# i2c-7segled-SOIC.net
KiCad netlist of a schematic drawn in EAGLE
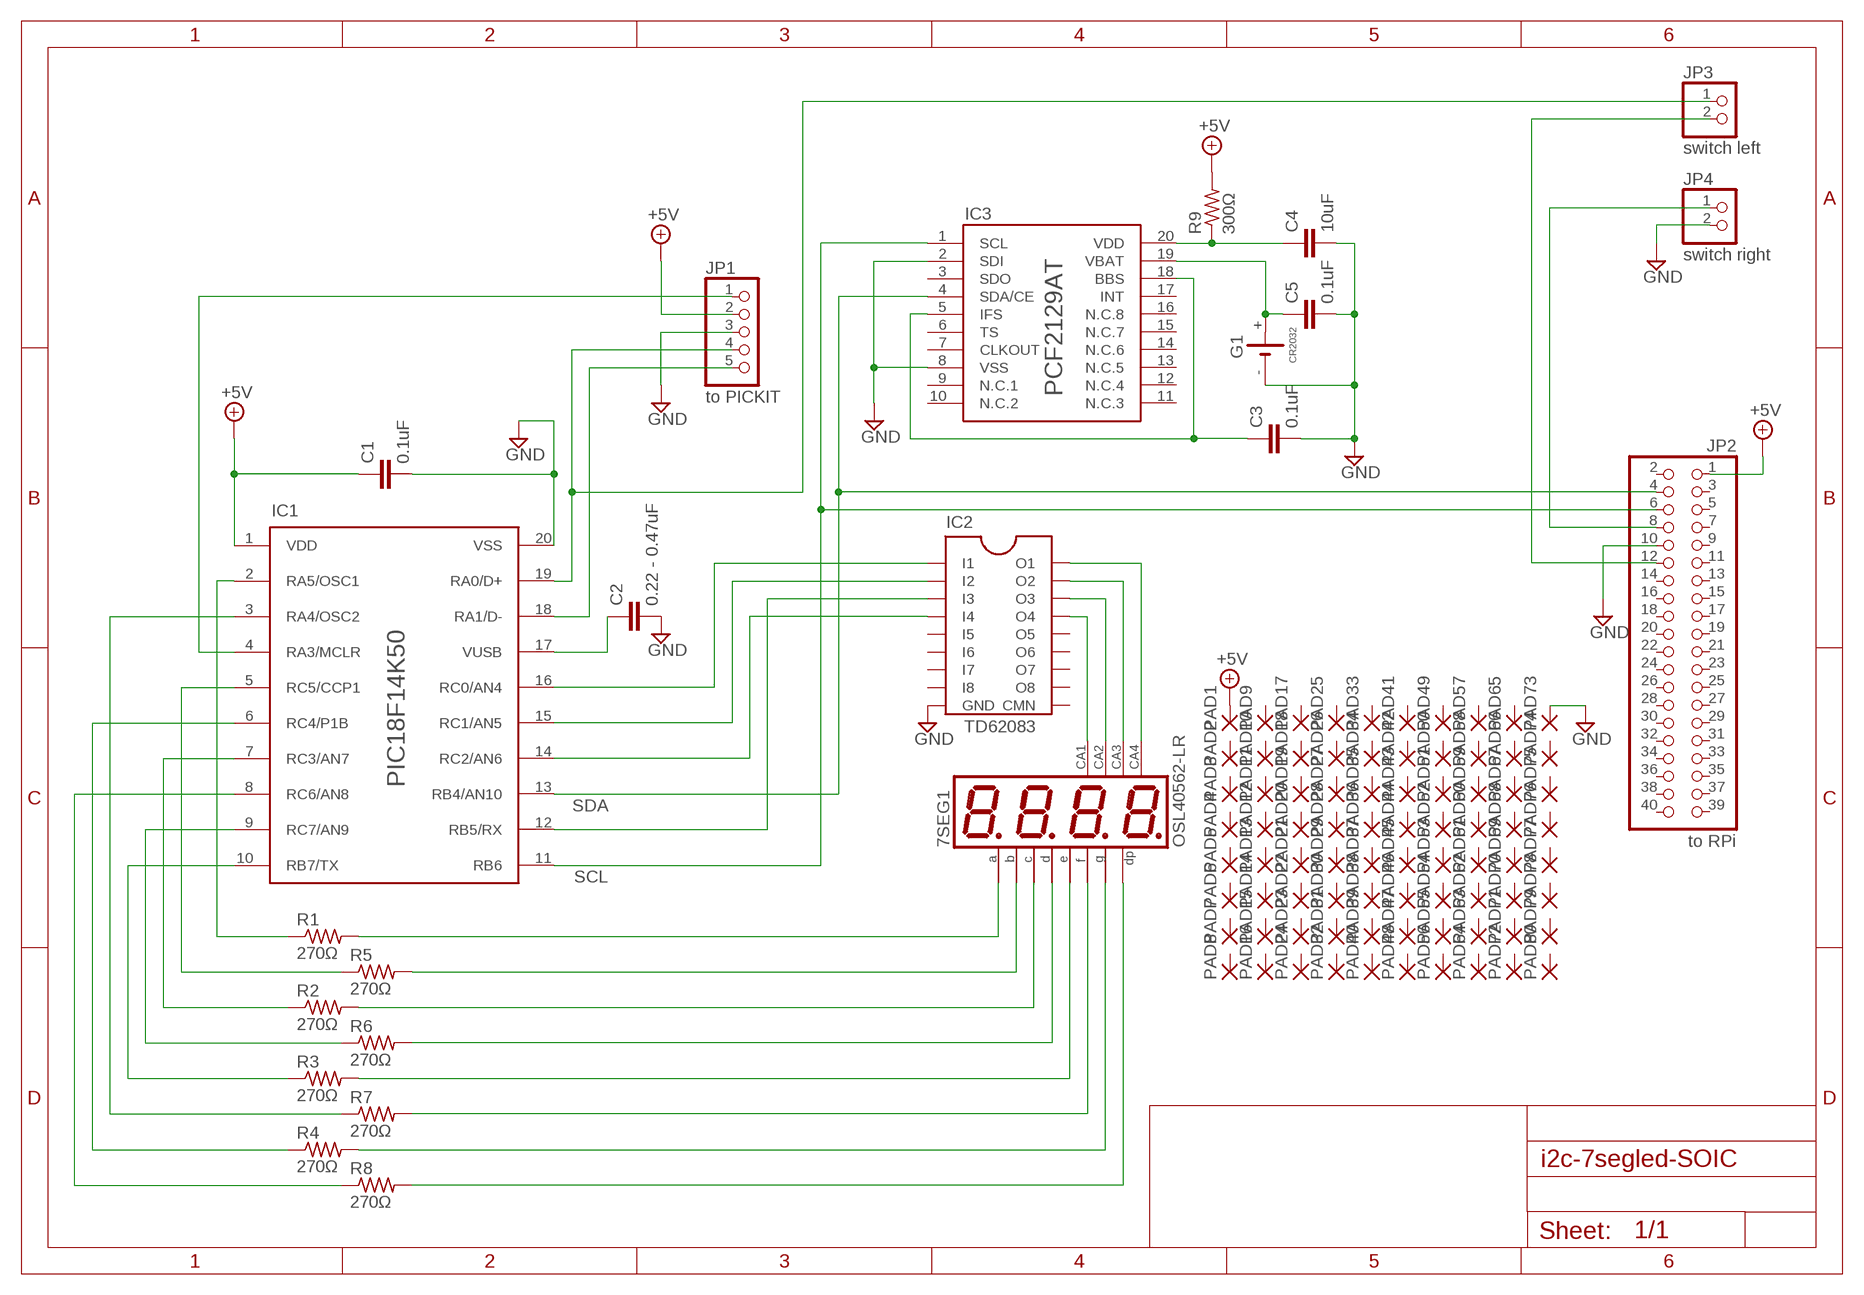
[diagram p0: schematic, sheet 1]

(export (version "E")
  (design (tool "Eeschema 10.0.6"))
  (components
    (comp (ref "7SEG1")
      (value "OSL40562-LR")
      (footprint "eagle-import:OSL40562")
      (libsource (lib "eagle-import") (part "OSL40562-?IR"))
    )
    (comp (ref "C1")
      (value "0.1uF")
      (footprint "eagle-import:C0504")
      (libsource (lib "eagle-import") (part "C-EUC0504"))
    )
    (comp (ref "C2")
      (value "0.22 - 0.47uF")
      (footprint "eagle-import:C0504")
      (libsource (lib "eagle-import") (part "C-EUC0504"))
    )
    (comp (ref "C3")
      (value "0.1uF")
      (footprint "eagle-import:C0504")
      (libsource (lib "eagle-import") (part "C-EUC0504"))
    )
    (comp (ref "C4")
      (value "10uF")
      (footprint "eagle-import:C0504")
      (libsource (lib "eagle-import") (part "C-EUC0504"))
    )
    (comp (ref "C5")
      (value "0.1uF")
      (footprint "eagle-import:C0504")
      (libsource (lib "eagle-import") (part "C-EUC0504"))
    )
    (comp (ref "G1")
      (value "CR2032")
      (footprint "eagle-import:HU2032")
      (libsource (lib "eagle-import") (part "HU2032"))
    )
    (comp (ref "IC1")
      (value "PIC18F14K50")
      (footprint "eagle-import:SO20")
      (libsource (lib "eagle-import") (part "PIC18F14K50-SO"))
    )
    (comp (ref "IC2")
      (value "TD62083")
      (footprint "eagle-import:SO18")
      (libsource (lib "eagle-import") (part "TD62083"))
    )
    (comp (ref "IC3")
      (value "PCF2129AT")
      (footprint "eagle-import:SO20")
      (libsource (lib "eagle-import") (part "PCF2129AT"))
    )
    (comp (ref "JP1")
      (value "to PICKIT")
      (footprint "eagle-import:1X05")
      (libsource (lib "eagle-import") (part "PINHD-1X5"))
    )
    (comp (ref "JP2")
      (value "to RPi")
      (footprint "eagle-import:2X20")
      (libsource (lib "eagle-import") (part "PINHD-2X20"))
    )
    (comp (ref "JP3")
      (value "switch left")
      (footprint "eagle-import:1X02")
      (libsource (lib "eagle-import") (part "PINHD-1X2"))
    )
    (comp (ref "JP4")
      (value "switch right")
      (footprint "eagle-import:1X02")
      (libsource (lib "eagle-import") (part "PINHD-1X2"))
    )
    (comp (ref "PAD1")
      (value "1,6/0,9")
      (footprint "eagle-import:1,6_0,9")
      (libsource (lib "eagle-import") (part "1,6/0,9"))
    )
    (comp (ref "PAD2")
      (value "1,6/0,9")
      (footprint "eagle-import:1,6_0,9")
      (libsource (lib "eagle-import") (part "1,6/0,9"))
    )
    (comp (ref "PAD3")
      (value "1,6/0,9")
      (footprint "eagle-import:1,6_0,9")
      (libsource (lib "eagle-import") (part "1,6/0,9"))
    )
    (comp (ref "PAD4")
      (value "1,6/0,9")
      (footprint "eagle-import:1,6_0,9")
      (libsource (lib "eagle-import") (part "1,6/0,9"))
    )
    (comp (ref "PAD5")
      (value "1,6/0,9")
      (footprint "eagle-import:1,6_0,9")
      (libsource (lib "eagle-import") (part "1,6/0,9"))
    )
    (comp (ref "PAD6")
      (value "1,6/0,9")
      (footprint "eagle-import:1,6_0,9")
      (libsource (lib "eagle-import") (part "1,6/0,9"))
    )
    (comp (ref "PAD7")
      (value "1,6/0,9")
      (footprint "eagle-import:1,6_0,9")
      (libsource (lib "eagle-import") (part "1,6/0,9"))
    )
    (comp (ref "PAD8")
      (value "1,6/0,9")
      (footprint "eagle-import:1,6_0,9")
      (libsource (lib "eagle-import") (part "1,6/0,9"))
    )
    (comp (ref "PAD9")
      (value "1,6/0,9")
      (footprint "eagle-import:1,6_0,9")
      (libsource (lib "eagle-import") (part "1,6/0,9"))
    )
    (comp (ref "PAD10")
      (value "1,6/0,9")
      (footprint "eagle-import:1,6_0,9")
      (libsource (lib "eagle-import") (part "1,6/0,9"))
    )
    (comp (ref "PAD11")
      (value "1,6/0,9")
      (footprint "eagle-import:1,6_0,9")
      (libsource (lib "eagle-import") (part "1,6/0,9"))
    )
    (comp (ref "PAD12")
      (value "1,6/0,9")
      (footprint "eagle-import:1,6_0,9")
      (libsource (lib "eagle-import") (part "1,6/0,9"))
    )
    (comp (ref "PAD13")
      (value "1,6/0,9")
      (footprint "eagle-import:1,6_0,9")
      (libsource (lib "eagle-import") (part "1,6/0,9"))
    )
    (comp (ref "PAD14")
      (value "1,6/0,9")
      (footprint "eagle-import:1,6_0,9")
      (libsource (lib "eagle-import") (part "1,6/0,9"))
    )
    (comp (ref "PAD15")
      (value "1,6/0,9")
      (footprint "eagle-import:1,6_0,9")
      (libsource (lib "eagle-import") (part "1,6/0,9"))
    )
    (comp (ref "PAD16")
      (value "1,6/0,9")
      (footprint "eagle-import:1,6_0,9")
      (libsource (lib "eagle-import") (part "1,6/0,9"))
    )
    (comp (ref "PAD17")
      (value "1,6/0,9")
      (footprint "eagle-import:1,6_0,9")
      (libsource (lib "eagle-import") (part "1,6/0,9"))
    )
    (comp (ref "PAD18")
      (value "1,6/0,9")
      (footprint "eagle-import:1,6_0,9")
      (libsource (lib "eagle-import") (part "1,6/0,9"))
    )
    (comp (ref "PAD19")
      (value "1,6/0,9")
      (footprint "eagle-import:1,6_0,9")
      (libsource (lib "eagle-import") (part "1,6/0,9"))
    )
    (comp (ref "PAD20")
      (value "1,6/0,9")
      (footprint "eagle-import:1,6_0,9")
      (libsource (lib "eagle-import") (part "1,6/0,9"))
    )
    (comp (ref "PAD21")
      (value "1,6/0,9")
      (footprint "eagle-import:1,6_0,9")
      (libsource (lib "eagle-import") (part "1,6/0,9"))
    )
    (comp (ref "PAD22")
      (value "1,6/0,9")
      (footprint "eagle-import:1,6_0,9")
      (libsource (lib "eagle-import") (part "1,6/0,9"))
    )
    (comp (ref "PAD23")
      (value "1,6/0,9")
      (footprint "eagle-import:1,6_0,9")
      (libsource (lib "eagle-import") (part "1,6/0,9"))
    )
    (comp (ref "PAD24")
      (value "1,6/0,9")
      (footprint "eagle-import:1,6_0,9")
      (libsource (lib "eagle-import") (part "1,6/0,9"))
    )
    (comp (ref "PAD25")
      (value "1,6/0,9")
      (footprint "eagle-import:1,6_0,9")
      (libsource (lib "eagle-import") (part "1,6/0,9"))
    )
    (comp (ref "PAD26")
      (value "1,6/0,9")
      (footprint "eagle-import:1,6_0,9")
      (libsource (lib "eagle-import") (part "1,6/0,9"))
    )
    (comp (ref "PAD27")
      (value "1,6/0,9")
      (footprint "eagle-import:1,6_0,9")
      (libsource (lib "eagle-import") (part "1,6/0,9"))
    )
    (comp (ref "PAD28")
      (value "1,6/0,9")
      (footprint "eagle-import:1,6_0,9")
      (libsource (lib "eagle-import") (part "1,6/0,9"))
    )
    (comp (ref "PAD29")
      (value "1,6/0,9")
      (footprint "eagle-import:1,6_0,9")
      (libsource (lib "eagle-import") (part "1,6/0,9"))
    )
    (comp (ref "PAD30")
      (value "1,6/0,9")
      (footprint "eagle-import:1,6_0,9")
      (libsource (lib "eagle-import") (part "1,6/0,9"))
    )
    (comp (ref "PAD31")
      (value "1,6/0,9")
      (footprint "eagle-import:1,6_0,9")
      (libsource (lib "eagle-import") (part "1,6/0,9"))
    )
    (comp (ref "PAD32")
      (value "1,6/0,9")
      (footprint "eagle-import:1,6_0,9")
      (libsource (lib "eagle-import") (part "1,6/0,9"))
    )
    (comp (ref "PAD33")
      (value "1,6/0,9")
      (footprint "eagle-import:1,6_0,9")
      (libsource (lib "eagle-import") (part "1,6/0,9"))
    )
    (comp (ref "PAD34")
      (value "1,6/0,9")
      (footprint "eagle-import:1,6_0,9")
      (libsource (lib "eagle-import") (part "1,6/0,9"))
    )
    (comp (ref "PAD35")
      (value "1,6/0,9")
      (footprint "eagle-import:1,6_0,9")
      (libsource (lib "eagle-import") (part "1,6/0,9"))
    )
    (comp (ref "PAD36")
      (value "1,6/0,9")
      (footprint "eagle-import:1,6_0,9")
      (libsource (lib "eagle-import") (part "1,6/0,9"))
    )
    (comp (ref "PAD37")
      (value "1,6/0,9")
      (footprint "eagle-import:1,6_0,9")
      (libsource (lib "eagle-import") (part "1,6/0,9"))
    )
    (comp (ref "PAD38")
      (value "1,6/0,9")
      (footprint "eagle-import:1,6_0,9")
      (libsource (lib "eagle-import") (part "1,6/0,9"))
    )
    (comp (ref "PAD39")
      (value "1,6/0,9")
      (footprint "eagle-import:1,6_0,9")
      (libsource (lib "eagle-import") (part "1,6/0,9"))
    )
    (comp (ref "PAD40")
      (value "1,6/0,9")
      (footprint "eagle-import:1,6_0,9")
      (libsource (lib "eagle-import") (part "1,6/0,9"))
    )
    (comp (ref "PAD41")
      (value "1,6/0,9")
      (footprint "eagle-import:1,6_0,9")
      (libsource (lib "eagle-import") (part "1,6/0,9"))
    )
    (comp (ref "PAD42")
      (value "1,6/0,9")
      (footprint "eagle-import:1,6_0,9")
      (libsource (lib "eagle-import") (part "1,6/0,9"))
    )
    (comp (ref "PAD43")
      (value "1,6/0,9")
      (footprint "eagle-import:1,6_0,9")
      (libsource (lib "eagle-import") (part "1,6/0,9"))
    )
    (comp (ref "PAD44")
      (value "1,6/0,9")
      (footprint "eagle-import:1,6_0,9")
      (libsource (lib "eagle-import") (part "1,6/0,9"))
    )
    (comp (ref "PAD45")
      (value "1,6/0,9")
      (footprint "eagle-import:1,6_0,9")
      (libsource (lib "eagle-import") (part "1,6/0,9"))
    )
    (comp (ref "PAD46")
      (value "1,6/0,9")
      (footprint "eagle-import:1,6_0,9")
      (libsource (lib "eagle-import") (part "1,6/0,9"))
    )
    (comp (ref "PAD47")
      (value "1,6/0,9")
      (footprint "eagle-import:1,6_0,9")
      (libsource (lib "eagle-import") (part "1,6/0,9"))
    )
    (comp (ref "PAD48")
      (value "1,6/0,9")
      (footprint "eagle-import:1,6_0,9")
      (libsource (lib "eagle-import") (part "1,6/0,9"))
    )
    (comp (ref "PAD49")
      (value "1,6/0,9")
      (footprint "eagle-import:1,6_0,9")
      (libsource (lib "eagle-import") (part "1,6/0,9"))
    )
    (comp (ref "PAD50")
      (value "1,6/0,9")
      (footprint "eagle-import:1,6_0,9")
      (libsource (lib "eagle-import") (part "1,6/0,9"))
    )
    (comp (ref "PAD51")
      (value "1,6/0,9")
      (footprint "eagle-import:1,6_0,9")
      (libsource (lib "eagle-import") (part "1,6/0,9"))
    )
    (comp (ref "PAD52")
      (value "1,6/0,9")
      (footprint "eagle-import:1,6_0,9")
      (libsource (lib "eagle-import") (part "1,6/0,9"))
    )
    (comp (ref "PAD53")
      (value "1,6/0,9")
      (footprint "eagle-import:1,6_0,9")
      (libsource (lib "eagle-import") (part "1,6/0,9"))
    )
    (comp (ref "PAD54")
      (value "1,6/0,9")
      (footprint "eagle-import:1,6_0,9")
      (libsource (lib "eagle-import") (part "1,6/0,9"))
    )
    (comp (ref "PAD55")
      (value "1,6/0,9")
      (footprint "eagle-import:1,6_0,9")
      (libsource (lib "eagle-import") (part "1,6/0,9"))
    )
    (comp (ref "PAD56")
      (value "1,6/0,9")
      (footprint "eagle-import:1,6_0,9")
      (libsource (lib "eagle-import") (part "1,6/0,9"))
    )
    (comp (ref "PAD57")
      (value "1,6/0,9")
      (footprint "eagle-import:1,6_0,9")
      (libsource (lib "eagle-import") (part "1,6/0,9"))
    )
    (comp (ref "PAD58")
      (value "1,6/0,9")
      (footprint "eagle-import:1,6_0,9")
      (libsource (lib "eagle-import") (part "1,6/0,9"))
    )
    (comp (ref "PAD59")
      (value "1,6/0,9")
      (footprint "eagle-import:1,6_0,9")
      (libsource (lib "eagle-import") (part "1,6/0,9"))
    )
    (comp (ref "PAD60")
      (value "1,6/0,9")
      (footprint "eagle-import:1,6_0,9")
      (libsource (lib "eagle-import") (part "1,6/0,9"))
    )
    (comp (ref "PAD61")
      (value "1,6/0,9")
      (footprint "eagle-import:1,6_0,9")
      (libsource (lib "eagle-import") (part "1,6/0,9"))
    )
    (comp (ref "PAD62")
      (value "1,6/0,9")
      (footprint "eagle-import:1,6_0,9")
      (libsource (lib "eagle-import") (part "1,6/0,9"))
    )
    (comp (ref "PAD63")
      (value "1,6/0,9")
      (footprint "eagle-import:1,6_0,9")
      (libsource (lib "eagle-import") (part "1,6/0,9"))
    )
    (comp (ref "PAD64")
      (value "1,6/0,9")
      (footprint "eagle-import:1,6_0,9")
      (libsource (lib "eagle-import") (part "1,6/0,9"))
    )
    (comp (ref "PAD65")
      (value "1,6/0,9")
      (footprint "eagle-import:1,6_0,9")
      (libsource (lib "eagle-import") (part "1,6/0,9"))
    )
    (comp (ref "PAD66")
      (value "1,6/0,9")
      (footprint "eagle-import:1,6_0,9")
      (libsource (lib "eagle-import") (part "1,6/0,9"))
    )
    (comp (ref "PAD67")
      (value "1,6/0,9")
      (footprint "eagle-import:1,6_0,9")
      (libsource (lib "eagle-import") (part "1,6/0,9"))
    )
    (comp (ref "PAD68")
      (value "1,6/0,9")
      (footprint "eagle-import:1,6_0,9")
      (libsource (lib "eagle-import") (part "1,6/0,9"))
    )
    (comp (ref "PAD69")
      (value "1,6/0,9")
      (footprint "eagle-import:1,6_0,9")
      (libsource (lib "eagle-import") (part "1,6/0,9"))
    )
    (comp (ref "PAD70")
      (value "1,6/0,9")
      (footprint "eagle-import:1,6_0,9")
      (libsource (lib "eagle-import") (part "1,6/0,9"))
    )
    (comp (ref "PAD71")
      (value "1,6/0,9")
      (footprint "eagle-import:1,6_0,9")
      (libsource (lib "eagle-import") (part "1,6/0,9"))
    )
    (comp (ref "PAD72")
      (value "1,6/0,9")
      (footprint "eagle-import:1,6_0,9")
      (libsource (lib "eagle-import") (part "1,6/0,9"))
    )
    (comp (ref "PAD73")
      (value "1,6/0,9")
      (footprint "eagle-import:1,6_0,9")
      (libsource (lib "eagle-import") (part "1,6/0,9"))
    )
    (comp (ref "PAD74")
      (value "1,6/0,9")
      (footprint "eagle-import:1,6_0,9")
      (libsource (lib "eagle-import") (part "1,6/0,9"))
    )
    (comp (ref "PAD75")
      (value "1,6/0,9")
      (footprint "eagle-import:1,6_0,9")
      (libsource (lib "eagle-import") (part "1,6/0,9"))
    )
    (comp (ref "PAD76")
      (value "1,6/0,9")
      (footprint "eagle-import:1,6_0,9")
      (libsource (lib "eagle-import") (part "1,6/0,9"))
    )
    (comp (ref "PAD77")
      (value "1,6/0,9")
      (footprint "eagle-import:1,6_0,9")
      (libsource (lib "eagle-import") (part "1,6/0,9"))
    )
    (comp (ref "PAD78")
      (value "1,6/0,9")
      (footprint "eagle-import:1,6_0,9")
      (libsource (lib "eagle-import") (part "1,6/0,9"))
    )
    (comp (ref "PAD79")
      (value "1,6/0,9")
      (footprint "eagle-import:1,6_0,9")
      (libsource (lib "eagle-import") (part "1,6/0,9"))
    )
    (comp (ref "PAD80")
      (value "1,6/0,9")
      (footprint "eagle-import:1,6_0,9")
      (libsource (lib "eagle-import") (part "1,6/0,9"))
    )
    (comp (ref "R1")
      (value "270Ω")
      (footprint "eagle-import:M0805")
      (libsource (lib "eagle-import") (part "R-US_M0805"))
    )
    (comp (ref "R2")
      (value "270Ω")
      (footprint "eagle-import:M0805")
      (libsource (lib "eagle-import") (part "R-US_M0805"))
    )
    (comp (ref "R3")
      (value "270Ω")
      (footprint "eagle-import:M0805")
      (libsource (lib "eagle-import") (part "R-US_M0805"))
    )
    (comp (ref "R4")
      (value "270Ω")
      (footprint "eagle-import:M0805")
      (libsource (lib "eagle-import") (part "R-US_M0805"))
    )
    (comp (ref "R5")
      (value "270Ω")
      (footprint "eagle-import:M0805")
      (libsource (lib "eagle-import") (part "R-US_M0805"))
    )
    (comp (ref "R6")
      (value "270Ω")
      (footprint "eagle-import:M0805")
      (libsource (lib "eagle-import") (part "R-US_M0805"))
    )
    (comp (ref "R7")
      (value "270Ω")
      (footprint "eagle-import:M0805")
      (libsource (lib "eagle-import") (part "R-US_M0805"))
    )
    (comp (ref "R8")
      (value "270Ω")
      (footprint "eagle-import:M0805")
      (libsource (lib "eagle-import") (part "R-US_M0805"))
    )
    (comp (ref "R9")
      (value "300Ω")
      (footprint "eagle-import:M0805")
      (libsource (lib "eagle-import") (part "R-US_M0805"))
    )
  )
  (nets
    (net (code "1") (name "+5V") (class "Default")
      (node (ref "C1") (pin "1") (pinfunction "1_1") (pintype "passive"))
      (node (ref "IC1") (pin "1") (pinfunction "VDD_1") (pintype "bidirectional"))
      (node (ref "JP1") (pin "2") (pinfunction "2_2") (pintype "passive"))
      (node (ref "JP2") (pin "1") (pinfunction "1_1") (pintype "passive"))
      (node (ref "PAD1") (pin "1") (pinfunction "P_1") (pintype "passive"))
      (node (ref "R9") (pin "2") (pinfunction "2_2") (pintype "passive"))
    )
    (net (code "2") (name "/SCL") (class "Default")
      (node (ref "IC1") (pin "13") (pinfunction "RB4/AN10_13") (pintype "bidirectional"))
      (node (ref "IC3") (pin "4") (pinfunction "SDA/CE_4") (pintype "bidirectional"))
      (node (ref "JP2") (pin "4") (pinfunction "4_4") (pintype "passive"))
    )
    (net (code "3") (name "GND") (class "Default")
      (node (ref "C1") (pin "2") (pinfunction "2_2") (pintype "passive"))
      (node (ref "C2") (pin "2") (pinfunction "2_2") (pintype "passive"))
      (node (ref "C3") (pin "2") (pinfunction "2_2") (pintype "passive"))
      (node (ref "C4") (pin "2") (pinfunction "2_2") (pintype "passive"))
      (node (ref "C5") (pin "2") (pinfunction "2_2") (pintype "passive"))
      (node (ref "G1") (pin "-") (pinfunction "-_-") (pintype "passive"))
      (node (ref "IC1") (pin "20") (pinfunction "VSS_20") (pintype "bidirectional"))
      (node (ref "IC2") (pin "9") (pinfunction "GND_9") (pintype "passive"))
      (node (ref "IC3") (pin "2") (pinfunction "SDI_2") (pintype "bidirectional"))
      (node (ref "IC3") (pin "8") (pinfunction "VSS_8") (pintype "bidirectional"))
      (node (ref "JP1") (pin "3") (pinfunction "3_3") (pintype "passive"))
      (node (ref "JP2") (pin "10") (pinfunction "10_10") (pintype "passive"))
      (node (ref "JP4") (pin "2") (pinfunction "2_2") (pintype "passive"))
      (node (ref "PAD73") (pin "1") (pinfunction "P_1") (pintype "passive"))
    )
    (net (code "4") (name "Net-(7SEG1-A)") (class "Default")
      (node (ref "7SEG1") (pin "11") (pinfunction "A_11") (pintype "passive"))
      (node (ref "R1") (pin "2") (pinfunction "2_2") (pintype "passive"))
    )
    (net (code "5") (name "Net-(7SEG1-B)") (class "Default")
      (node (ref "7SEG1") (pin "7") (pinfunction "B_7") (pintype "passive"))
      (node (ref "R5") (pin "2") (pinfunction "2_2") (pintype "passive"))
    )
    (net (code "6") (name "Net-(7SEG1-C)") (class "Default")
      (node (ref "7SEG1") (pin "4") (pinfunction "C_4") (pintype "passive"))
      (node (ref "R2") (pin "2") (pinfunction "2_2") (pintype "passive"))
    )
    (net (code "7") (name "Net-(7SEG1-D)") (class "Default")
      (node (ref "7SEG1") (pin "2") (pinfunction "D_2") (pintype "passive"))
      (node (ref "R6") (pin "2") (pinfunction "2_2") (pintype "passive"))
    )
    (net (code "8") (name "Net-(7SEG1-DP)") (class "Default")
      (node (ref "7SEG1") (pin "3") (pinfunction "DP_3") (pintype "passive"))
      (node (ref "R8") (pin "2") (pinfunction "2_2") (pintype "passive"))
    )
    (net (code "9") (name "Net-(7SEG1-E)") (class "Default")
      (node (ref "7SEG1") (pin "1") (pinfunction "E_1") (pintype "passive"))
      (node (ref "R3") (pin "2") (pinfunction "2_2") (pintype "passive"))
    )
    (net (code "10") (name "Net-(7SEG1-F)") (class "Default")
      (node (ref "7SEG1") (pin "10") (pinfunction "F_10") (pintype "passive"))
      (node (ref "R7") (pin "2") (pinfunction "2_2") (pintype "passive"))
    )
    (net (code "11") (name "Net-(7SEG1-G)") (class "Default")
      (node (ref "7SEG1") (pin "5") (pinfunction "G_5") (pintype "passive"))
      (node (ref "R4") (pin "2") (pinfunction "2_2") (pintype "passive"))
    )
    (net (code "12") (name "Net-(IC1-RA0{slash}D+)") (class "Default")
      (node (ref "IC1") (pin "19") (pinfunction "RA0/D+_19") (pintype "bidirectional"))
      (node (ref "JP1") (pin "4") (pinfunction "4_4") (pintype "passive"))
      (node (ref "JP3") (pin "1") (pinfunction "1_1") (pintype "passive"))
    )
    (net (code "13") (name "Net-(IC1-RA1{slash}D-)") (class "Default")
      (node (ref "IC1") (pin "18") (pinfunction "RA1/D-_18") (pintype "bidirectional"))
      (node (ref "JP1") (pin "5") (pinfunction "5_5") (pintype "passive"))
    )
    (net (code "14") (name "Net-(IC1-RA3{slash}MCLR)") (class "Default")
      (node (ref "IC1") (pin "4") (pinfunction "RA3/MCLR_4") (pintype "bidirectional"))
      (node (ref "JP1") (pin "1") (pinfunction "1_1") (pintype "passive"))
    )
    (net (code "15") (name "Net-(IC1-RA4{slash}OSC2)") (class "Default")
      (node (ref "IC1") (pin "3") (pinfunction "RA4/OSC2_3") (pintype "bidirectional"))
      (node (ref "R7") (pin "1") (pinfunction "1_1") (pintype "passive"))
    )
    (net (code "16") (name "Net-(IC1-RA5{slash}OSC1)") (class "Default")
      (node (ref "IC1") (pin "2") (pinfunction "RA5/OSC1_2") (pintype "bidirectional"))
      (node (ref "R1") (pin "1") (pinfunction "1_1") (pintype "passive"))
    )
    (net (code "17") (name "Net-(IC1-RB5{slash}RX)") (class "Default")
      (node (ref "IC1") (pin "12") (pinfunction "RB5/RX_12") (pintype "bidirectional"))
      (node (ref "IC2") (pin "3") (pinfunction "I3_3") (pintype "passive"))
    )
    (net (code "18") (name "Net-(IC1-RB6)") (class "Default")
      (node (ref "IC1") (pin "11") (pinfunction "RB6_11") (pintype "bidirectional"))
      (node (ref "IC3") (pin "1") (pinfunction "SCL_1") (pintype "bidirectional"))
      (node (ref "JP2") (pin "6") (pinfunction "6_6") (pintype "passive"))
    )
    (net (code "19") (name "Net-(IC1-RB7{slash}TX)") (class "Default")
      (node (ref "IC1") (pin "10") (pinfunction "RB7/TX_10") (pintype "bidirectional"))
      (node (ref "R3") (pin "1") (pinfunction "1_1") (pintype "passive"))
    )
    (net (code "20") (name "Net-(IC1-RC0{slash}AN4)") (class "Default")
      (node (ref "IC1") (pin "16") (pinfunction "RC0/AN4_16") (pintype "bidirectional"))
      (node (ref "IC2") (pin "1") (pinfunction "I1_1") (pintype "passive"))
    )
    (net (code "21") (name "Net-(IC1-RC1{slash}AN5)") (class "Default")
      (node (ref "IC1") (pin "15") (pinfunction "RC1/AN5_15") (pintype "bidirectional"))
      (node (ref "IC2") (pin "2") (pinfunction "I2_2") (pintype "passive"))
    )
    (net (code "22") (name "Net-(IC1-RC2{slash}AN6)") (class "Default")
      (node (ref "IC1") (pin "14") (pinfunction "RC2/AN6_14") (pintype "bidirectional"))
      (node (ref "IC2") (pin "4") (pinfunction "I4_4") (pintype "passive"))
    )
    (net (code "23") (name "Net-(IC1-RC3{slash}AN7)") (class "Default")
      (node (ref "IC1") (pin "7") (pinfunction "RC3/AN7_7") (pintype "bidirectional"))
      (node (ref "R2") (pin "1") (pinfunction "1_1") (pintype "passive"))
    )
    (net (code "24") (name "Net-(IC1-RC4{slash}P1B)") (class "Default")
      (node (ref "IC1") (pin "6") (pinfunction "RC4/P1B_6") (pintype "bidirectional"))
      (node (ref "R4") (pin "1") (pinfunction "1_1") (pintype "passive"))
    )
    (net (code "25") (name "Net-(IC1-RC5{slash}CCP1)") (class "Default")
      (node (ref "IC1") (pin "5") (pinfunction "RC5/CCP1_5") (pintype "bidirectional"))
      (node (ref "R5") (pin "1") (pinfunction "1_1") (pintype "passive"))
    )
    (net (code "26") (name "Net-(IC1-RC6{slash}AN8)") (class "Default")
      (node (ref "IC1") (pin "8") (pinfunction "RC6/AN8_8") (pintype "bidirectional"))
      (node (ref "R8") (pin "1") (pinfunction "1_1") (pintype "passive"))
    )
    (net (code "27") (name "Net-(IC1-RC7{slash}AN9)") (class "Default")
      (node (ref "IC1") (pin "9") (pinfunction "RC7/AN9_9") (pintype "bidirectional"))
      (node (ref "R6") (pin "1") (pinfunction "1_1") (pintype "passive"))
    )
    (net (code "28") (name "Net-(IC1-VUSB)") (class "Default")
      (node (ref "C2") (pin "1") (pinfunction "1_1") (pintype "passive"))
      (node (ref "IC1") (pin "17") (pinfunction "VUSB_17") (pintype "bidirectional"))
    )
    (net (code "29") (name "Net-(IC2-O1)") (class "Default")
      (node (ref "7SEG1") (pin "6") (pinfunction "CA_6") (pintype "passive"))
      (node (ref "IC2") (pin "18") (pinfunction "O1_18") (pintype "passive"))
    )
    (net (code "30") (name "Net-(IC2-O2)") (class "Default")
      (node (ref "7SEG1") (pin "8") (pinfunction "CA_8") (pintype "passive"))
      (node (ref "IC2") (pin "17") (pinfunction "O2_17") (pintype "passive"))
    )
    (net (code "31") (name "Net-(IC2-O3)") (class "Default")
      (node (ref "7SEG1") (pin "9") (pinfunction "CA_9") (pintype "passive"))
      (node (ref "IC2") (pin "16") (pinfunction "O3_16") (pintype "passive"))
    )
    (net (code "32") (name "Net-(IC2-O4)") (class "Default")
      (node (ref "7SEG1") (pin "12") (pinfunction "CA_12") (pintype "passive"))
      (node (ref "IC2") (pin "15") (pinfunction "O4_15") (pintype "passive"))
    )
    (net (code "33") (name "Net-(IC3-BBS)") (class "Default")
      (node (ref "C3") (pin "1") (pinfunction "1_1") (pintype "passive"))
      (node (ref "IC3") (pin "18") (pinfunction "BBS_18") (pintype "bidirectional"))
      (node (ref "IC3") (pin "5") (pinfunction "IFS_5") (pintype "bidirectional"))
    )
    (net (code "34") (name "Net-(IC3-VBAT)") (class "Default")
      (node (ref "C5") (pin "1") (pinfunction "1_1") (pintype "passive"))
      (node (ref "G1") (pin "+") (pinfunction "+_+") (pintype "passive"))
      (node (ref "IC3") (pin "19") (pinfunction "VBAT_19") (pintype "bidirectional"))
    )
    (net (code "35") (name "Net-(IC3-VDD)") (class "Default")
      (node (ref "C4") (pin "1") (pinfunction "1_1") (pintype "passive"))
      (node (ref "IC3") (pin "20") (pinfunction "VDD_20") (pintype "bidirectional"))
      (node (ref "R9") (pin "1") (pinfunction "1_1") (pintype "passive"))
    )
    (net (code "36") (name "Net-(JP2-Pad8)") (class "Default")
      (node (ref "JP2") (pin "8") (pinfunction "8_8") (pintype "passive"))
      (node (ref "JP4") (pin "1") (pinfunction "1_1") (pintype "passive"))
    )
    (net (code "37") (name "Net-(JP2-Pad12)") (class "Default")
      (node (ref "JP2") (pin "12") (pinfunction "12_12") (pintype "passive"))
      (node (ref "JP3") (pin "2") (pinfunction "2_2") (pintype "passive"))
    )
    (net (code "38") (name "unconnected-(G1-+-Pad+@2)") (class "Default")
      (node (ref "G1") (pin "+@2") (pinfunction "+_+@2") (pintype "passive"))
    )
    (net (code "39") (name "unconnected-(IC2-CMN-Pad10)") (class "Default")
      (node (ref "IC2") (pin "10") (pinfunction "CMN_10") (pintype "passive"))
    )
    (net (code "40") (name "unconnected-(IC2-I5-Pad5)") (class "Default")
      (node (ref "IC2") (pin "5") (pinfunction "I5_5") (pintype "passive"))
    )
    (net (code "41") (name "unconnected-(IC2-I6-Pad6)") (class "Default")
      (node (ref "IC2") (pin "6") (pinfunction "I6_6") (pintype "passive"))
    )
    (net (code "42") (name "unconnected-(IC2-I7-Pad7)") (class "Default")
      (node (ref "IC2") (pin "7") (pinfunction "I7_7") (pintype "passive"))
    )
    (net (code "43") (name "unconnected-(IC2-I8-Pad8)") (class "Default")
      (node (ref "IC2") (pin "8") (pinfunction "I8_8") (pintype "passive"))
    )
    (net (code "44") (name "unconnected-(IC2-O5-Pad14)") (class "Default")
      (node (ref "IC2") (pin "14") (pinfunction "O5_14") (pintype "passive"))
    )
    (net (code "45") (name "unconnected-(IC2-O6-Pad13)") (class "Default")
      (node (ref "IC2") (pin "13") (pinfunction "O6_13") (pintype "passive"))
    )
    (net (code "46") (name "unconnected-(IC2-O7-Pad12)") (class "Default")
      (node (ref "IC2") (pin "12") (pinfunction "O7_12") (pintype "passive"))
    )
    (net (code "47") (name "unconnected-(IC2-O8-Pad11)") (class "Default")
      (node (ref "IC2") (pin "11") (pinfunction "O8_11") (pintype "passive"))
    )
    (net (code "48") (name "unconnected-(IC3-CLKOUT-Pad7)") (class "Default")
      (node (ref "IC3") (pin "7") (pinfunction "CLKOUT_7") (pintype "bidirectional"))
    )
    (net (code "49") (name "unconnected-(IC3-INT-Pad17)") (class "Default")
      (node (ref "IC3") (pin "17") (pinfunction "INT_17") (pintype "bidirectional"))
    )
    (net (code "50") (name "unconnected-(IC3-N.C.1-Pad9)") (class "Default")
      (node (ref "IC3") (pin "9") (pinfunction "N.C.1_9") (pintype "bidirectional"))
    )
    (net (code "51") (name "unconnected-(IC3-N.C.2-Pad10)") (class "Default")
      (node (ref "IC3") (pin "10") (pinfunction "N.C.2_10") (pintype "bidirectional"))
    )
    (net (code "52") (name "unconnected-(IC3-N.C.3-Pad11)") (class "Default")
      (node (ref "IC3") (pin "11") (pinfunction "N.C.3_11") (pintype "bidirectional"))
    )
    (net (code "53") (name "unconnected-(IC3-N.C.4-Pad12)") (class "Default")
      (node (ref "IC3") (pin "12") (pinfunction "N.C.4_12") (pintype "bidirectional"))
    )
    (net (code "54") (name "unconnected-(IC3-N.C.5-Pad13)") (class "Default")
      (node (ref "IC3") (pin "13") (pinfunction "N.C.5_13") (pintype "bidirectional"))
    )
    (net (code "55") (name "unconnected-(IC3-N.C.6-Pad14)") (class "Default")
      (node (ref "IC3") (pin "14") (pinfunction "N.C.6_14") (pintype "bidirectional"))
    )
    (net (code "56") (name "unconnected-(IC3-N.C.7-Pad15)") (class "Default")
      (node (ref "IC3") (pin "15") (pinfunction "N.C.7_15") (pintype "bidirectional"))
    )
    (net (code "57") (name "unconnected-(IC3-N.C.8-Pad16)") (class "Default")
      (node (ref "IC3") (pin "16") (pinfunction "N.C.8_16") (pintype "bidirectional"))
    )
    (net (code "58") (name "unconnected-(IC3-SDO-Pad3)") (class "Default")
      (node (ref "IC3") (pin "3") (pinfunction "SDO_3") (pintype "bidirectional"))
    )
    (net (code "59") (name "unconnected-(IC3-TS-Pad6)") (class "Default")
      (node (ref "IC3") (pin "6") (pinfunction "TS_6") (pintype "bidirectional"))
    )
    (net (code "60") (name "unconnected-(JP2-Pad2)") (class "Default")
      (node (ref "JP2") (pin "2") (pinfunction "2_2") (pintype "passive"))
    )
    (net (code "61") (name "unconnected-(JP2-Pad3)") (class "Default")
      (node (ref "JP2") (pin "3") (pinfunction "3_3") (pintype "passive"))
    )
    (net (code "62") (name "unconnected-(JP2-Pad5)") (class "Default")
      (node (ref "JP2") (pin "5") (pinfunction "5_5") (pintype "passive"))
    )
    (net (code "63") (name "unconnected-(JP2-Pad7)") (class "Default")
      (node (ref "JP2") (pin "7") (pinfunction "7_7") (pintype "passive"))
    )
    (net (code "64") (name "unconnected-(JP2-Pad9)") (class "Default")
      (node (ref "JP2") (pin "9") (pinfunction "9_9") (pintype "passive"))
    )
    (net (code "65") (name "unconnected-(JP2-Pad11)") (class "Default")
      (node (ref "JP2") (pin "11") (pinfunction "11_11") (pintype "passive"))
    )
    (net (code "66") (name "unconnected-(JP2-Pad13)") (class "Default")
      (node (ref "JP2") (pin "13") (pinfunction "13_13") (pintype "passive"))
    )
    (net (code "67") (name "unconnected-(JP2-Pad14)") (class "Default")
      (node (ref "JP2") (pin "14") (pinfunction "14_14") (pintype "passive"))
    )
    (net (code "68") (name "unconnected-(JP2-Pad15)") (class "Default")
      (node (ref "JP2") (pin "15") (pinfunction "15_15") (pintype "passive"))
    )
    (net (code "69") (name "unconnected-(JP2-Pad16)") (class "Default")
      (node (ref "JP2") (pin "16") (pinfunction "16_16") (pintype "passive"))
    )
    (net (code "70") (name "unconnected-(JP2-Pad17)") (class "Default")
      (node (ref "JP2") (pin "17") (pinfunction "17_17") (pintype "passive"))
    )
    (net (code "71") (name "unconnected-(JP2-Pad18)") (class "Default")
      (node (ref "JP2") (pin "18") (pinfunction "18_18") (pintype "passive"))
    )
    (net (code "72") (name "unconnected-(JP2-Pad19)") (class "Default")
      (node (ref "JP2") (pin "19") (pinfunction "19_19") (pintype "passive"))
    )
    (net (code "73") (name "unconnected-(JP2-Pad20)") (class "Default")
      (node (ref "JP2") (pin "20") (pinfunction "20_20") (pintype "passive"))
    )
    (net (code "74") (name "unconnected-(JP2-Pad21)") (class "Default")
      (node (ref "JP2") (pin "21") (pinfunction "21_21") (pintype "passive"))
    )
    (net (code "75") (name "unconnected-(JP2-Pad22)") (class "Default")
      (node (ref "JP2") (pin "22") (pinfunction "22_22") (pintype "passive"))
    )
    (net (code "76") (name "unconnected-(JP2-Pad23)") (class "Default")
      (node (ref "JP2") (pin "23") (pinfunction "23_23") (pintype "passive"))
    )
    (net (code "77") (name "unconnected-(JP2-Pad24)") (class "Default")
      (node (ref "JP2") (pin "24") (pinfunction "24_24") (pintype "passive"))
    )
    (net (code "78") (name "unconnected-(JP2-Pad25)") (class "Default")
      (node (ref "JP2") (pin "25") (pinfunction "25_25") (pintype "passive"))
    )
    (net (code "79") (name "unconnected-(JP2-Pad26)") (class "Default")
      (node (ref "JP2") (pin "26") (pinfunction "26_26") (pintype "passive"))
    )
    (net (code "80") (name "unconnected-(JP2-Pad27)") (class "Default")
      (node (ref "JP2") (pin "27") (pinfunction "27_27") (pintype "passive"))
    )
    (net (code "81") (name "unconnected-(JP2-Pad28)") (class "Default")
      (node (ref "JP2") (pin "28") (pinfunction "28_28") (pintype "passive"))
    )
    (net (code "82") (name "unconnected-(JP2-Pad29)") (class "Default")
      (node (ref "JP2") (pin "29") (pinfunction "29_29") (pintype "passive"))
    )
    (net (code "83") (name "unconnected-(JP2-Pad30)") (class "Default")
      (node (ref "JP2") (pin "30") (pinfunction "30_30") (pintype "passive"))
    )
    (net (code "84") (name "unconnected-(JP2-Pad31)") (class "Default")
      (node (ref "JP2") (pin "31") (pinfunction "31_31") (pintype "passive"))
    )
    (net (code "85") (name "unconnected-(JP2-Pad32)") (class "Default")
      (node (ref "JP2") (pin "32") (pinfunction "32_32") (pintype "passive"))
    )
    (net (code "86") (name "unconnected-(JP2-Pad33)") (class "Default")
      (node (ref "JP2") (pin "33") (pinfunction "33_33") (pintype "passive"))
    )
    (net (code "87") (name "unconnected-(JP2-Pad34)") (class "Default")
      (node (ref "JP2") (pin "34") (pinfunction "34_34") (pintype "passive"))
    )
    (net (code "88") (name "unconnected-(JP2-Pad35)") (class "Default")
      (node (ref "JP2") (pin "35") (pinfunction "35_35") (pintype "passive"))
    )
    (net (code "89") (name "unconnected-(JP2-Pad36)") (class "Default")
      (node (ref "JP2") (pin "36") (pinfunction "36_36") (pintype "passive"))
    )
    (net (code "90") (name "unconnected-(JP2-Pad37)") (class "Default")
      (node (ref "JP2") (pin "37") (pinfunction "37_37") (pintype "passive"))
    )
    (net (code "91") (name "unconnected-(JP2-Pad38)") (class "Default")
      (node (ref "JP2") (pin "38") (pinfunction "38_38") (pintype "passive"))
    )
    (net (code "92") (name "unconnected-(JP2-Pad39)") (class "Default")
      (node (ref "JP2") (pin "39") (pinfunction "39_39") (pintype "passive"))
    )
    (net (code "93") (name "unconnected-(JP2-Pad40)") (class "Default")
      (node (ref "JP2") (pin "40") (pinfunction "40_40") (pintype "passive"))
    )
    (net (code "94") (name "unconnected-(PAD2-P-Pad1)") (class "Default")
      (node (ref "PAD2") (pin "1") (pinfunction "P_1") (pintype "passive"))
    )
    (net (code "95") (name "unconnected-(PAD3-P-Pad1)") (class "Default")
      (node (ref "PAD3") (pin "1") (pinfunction "P_1") (pintype "passive"))
    )
    (net (code "96") (name "unconnected-(PAD4-P-Pad1)") (class "Default")
      (node (ref "PAD4") (pin "1") (pinfunction "P_1") (pintype "passive"))
    )
    (net (code "97") (name "unconnected-(PAD5-P-Pad1)") (class "Default")
      (node (ref "PAD5") (pin "1") (pinfunction "P_1") (pintype "passive"))
    )
    (net (code "98") (name "unconnected-(PAD6-P-Pad1)") (class "Default")
      (node (ref "PAD6") (pin "1") (pinfunction "P_1") (pintype "passive"))
    )
    (net (code "99") (name "unconnected-(PAD7-P-Pad1)") (class "Default")
      (node (ref "PAD7") (pin "1") (pinfunction "P_1") (pintype "passive"))
    )
    (net (code "100") (name "unconnected-(PAD8-P-Pad1)") (class "Default")
      (node (ref "PAD8") (pin "1") (pinfunction "P_1") (pintype "passive"))
    )
    (net (code "101") (name "unconnected-(PAD9-P-Pad1)") (class "Default")
      (node (ref "PAD9") (pin "1") (pinfunction "P_1") (pintype "passive"))
    )
    (net (code "102") (name "unconnected-(PAD10-P-Pad1)") (class "Default")
      (node (ref "PAD10") (pin "1") (pinfunction "P_1") (pintype "passive"))
    )
    (net (code "103") (name "unconnected-(PAD11-P-Pad1)") (class "Default")
      (node (ref "PAD11") (pin "1") (pinfunction "P_1") (pintype "passive"))
    )
    (net (code "104") (name "unconnected-(PAD12-P-Pad1)") (class "Default")
      (node (ref "PAD12") (pin "1") (pinfunction "P_1") (pintype "passive"))
    )
    (net (code "105") (name "unconnected-(PAD13-P-Pad1)") (class "Default")
      (node (ref "PAD13") (pin "1") (pinfunction "P_1") (pintype "passive"))
    )
    (net (code "106") (name "unconnected-(PAD14-P-Pad1)") (class "Default")
      (node (ref "PAD14") (pin "1") (pinfunction "P_1") (pintype "passive"))
    )
    (net (code "107") (name "unconnected-(PAD15-P-Pad1)") (class "Default")
      (node (ref "PAD15") (pin "1") (pinfunction "P_1") (pintype "passive"))
    )
    (net (code "108") (name "unconnected-(PAD16-P-Pad1)") (class "Default")
      (node (ref "PAD16") (pin "1") (pinfunction "P_1") (pintype "passive"))
    )
    (net (code "109") (name "unconnected-(PAD17-P-Pad1)") (class "Default")
      (node (ref "PAD17") (pin "1") (pinfunction "P_1") (pintype "passive"))
    )
    (net (code "110") (name "unconnected-(PAD18-P-Pad1)") (class "Default")
      (node (ref "PAD18") (pin "1") (pinfunction "P_1") (pintype "passive"))
    )
    (net (code "111") (name "unconnected-(PAD19-P-Pad1)") (class "Default")
      (node (ref "PAD19") (pin "1") (pinfunction "P_1") (pintype "passive"))
    )
    (net (code "112") (name "unconnected-(PAD20-P-Pad1)") (class "Default")
      (node (ref "PAD20") (pin "1") (pinfunction "P_1") (pintype "passive"))
    )
    (net (code "113") (name "unconnected-(PAD21-P-Pad1)") (class "Default")
      (node (ref "PAD21") (pin "1") (pinfunction "P_1") (pintype "passive"))
    )
    (net (code "114") (name "unconnected-(PAD22-P-Pad1)") (class "Default")
      (node (ref "PAD22") (pin "1") (pinfunction "P_1") (pintype "passive"))
    )
    (net (code "115") (name "unconnected-(PAD23-P-Pad1)") (class "Default")
      (node (ref "PAD23") (pin "1") (pinfunction "P_1") (pintype "passive"))
    )
    (net (code "116") (name "unconnected-(PAD24-P-Pad1)") (class "Default")
      (node (ref "PAD24") (pin "1") (pinfunction "P_1") (pintype "passive"))
    )
    (net (code "117") (name "unconnected-(PAD25-P-Pad1)") (class "Default")
      (node (ref "PAD25") (pin "1") (pinfunction "P_1") (pintype "passive"))
    )
    (net (code "118") (name "unconnected-(PAD26-P-Pad1)") (class "Default")
      (node (ref "PAD26") (pin "1") (pinfunction "P_1") (pintype "passive"))
    )
    (net (code "119") (name "unconnected-(PAD27-P-Pad1)") (class "Default")
      (node (ref "PAD27") (pin "1") (pinfunction "P_1") (pintype "passive"))
    )
    (net (code "120") (name "unconnected-(PAD28-P-Pad1)") (class "Default")
      (node (ref "PAD28") (pin "1") (pinfunction "P_1") (pintype "passive"))
    )
    (net (code "121") (name "unconnected-(PAD29-P-Pad1)") (class "Default")
      (node (ref "PAD29") (pin "1") (pinfunction "P_1") (pintype "passive"))
    )
    (net (code "122") (name "unconnected-(PAD30-P-Pad1)") (class "Default")
      (node (ref "PAD30") (pin "1") (pinfunction "P_1") (pintype "passive"))
    )
    (net (code "123") (name "unconnected-(PAD31-P-Pad1)") (class "Default")
      (node (ref "PAD31") (pin "1") (pinfunction "P_1") (pintype "passive"))
    )
    (net (code "124") (name "unconnected-(PAD32-P-Pad1)") (class "Default")
      (node (ref "PAD32") (pin "1") (pinfunction "P_1") (pintype "passive"))
    )
    (net (code "125") (name "unconnected-(PAD33-P-Pad1)") (class "Default")
      (node (ref "PAD33") (pin "1") (pinfunction "P_1") (pintype "passive"))
    )
    (net (code "126") (name "unconnected-(PAD34-P-Pad1)") (class "Default")
      (node (ref "PAD34") (pin "1") (pinfunction "P_1") (pintype "passive"))
    )
    (net (code "127") (name "unconnected-(PAD35-P-Pad1)") (class "Default")
      (node (ref "PAD35") (pin "1") (pinfunction "P_1") (pintype "passive"))
    )
    (net (code "128") (name "unconnected-(PAD36-P-Pad1)") (class "Default")
      (node (ref "PAD36") (pin "1") (pinfunction "P_1") (pintype "passive"))
    )
    (net (code "129") (name "unconnected-(PAD37-P-Pad1)") (class "Default")
      (node (ref "PAD37") (pin "1") (pinfunction "P_1") (pintype "passive"))
    )
    (net (code "130") (name "unconnected-(PAD38-P-Pad1)") (class "Default")
      (node (ref "PAD38") (pin "1") (pinfunction "P_1") (pintype "passive"))
    )
    (net (code "131") (name "unconnected-(PAD39-P-Pad1)") (class "Default")
      (node (ref "PAD39") (pin "1") (pinfunction "P_1") (pintype "passive"))
    )
    (net (code "132") (name "unconnected-(PAD40-P-Pad1)") (class "Default")
      (node (ref "PAD40") (pin "1") (pinfunction "P_1") (pintype "passive"))
    )
    (net (code "133") (name "unconnected-(PAD41-P-Pad1)") (class "Default")
      (node (ref "PAD41") (pin "1") (pinfunction "P_1") (pintype "passive"))
    )
    (net (code "134") (name "unconnected-(PAD42-P-Pad1)") (class "Default")
      (node (ref "PAD42") (pin "1") (pinfunction "P_1") (pintype "passive"))
    )
    (net (code "135") (name "unconnected-(PAD43-P-Pad1)") (class "Default")
      (node (ref "PAD43") (pin "1") (pinfunction "P_1") (pintype "passive"))
    )
    (net (code "136") (name "unconnected-(PAD44-P-Pad1)") (class "Default")
      (node (ref "PAD44") (pin "1") (pinfunction "P_1") (pintype "passive"))
    )
    (net (code "137") (name "unconnected-(PAD45-P-Pad1)") (class "Default")
      (node (ref "PAD45") (pin "1") (pinfunction "P_1") (pintype "passive"))
    )
    (net (code "138") (name "unconnected-(PAD46-P-Pad1)") (class "Default")
      (node (ref "PAD46") (pin "1") (pinfunction "P_1") (pintype "passive"))
    )
    (net (code "139") (name "unconnected-(PAD47-P-Pad1)") (class "Default")
      (node (ref "PAD47") (pin "1") (pinfunction "P_1") (pintype "passive"))
    )
    (net (code "140") (name "unconnected-(PAD48-P-Pad1)") (class "Default")
      (node (ref "PAD48") (pin "1") (pinfunction "P_1") (pintype "passive"))
    )
    (net (code "141") (name "unconnected-(PAD49-P-Pad1)") (class "Default")
      (node (ref "PAD49") (pin "1") (pinfunction "P_1") (pintype "passive"))
    )
    (net (code "142") (name "unconnected-(PAD50-P-Pad1)") (class "Default")
      (node (ref "PAD50") (pin "1") (pinfunction "P_1") (pintype "passive"))
    )
    (net (code "143") (name "unconnected-(PAD51-P-Pad1)") (class "Default")
      (node (ref "PAD51") (pin "1") (pinfunction "P_1") (pintype "passive"))
    )
    (net (code "144") (name "unconnected-(PAD52-P-Pad1)") (class "Default")
      (node (ref "PAD52") (pin "1") (pinfunction "P_1") (pintype "passive"))
    )
    (net (code "145") (name "unconnected-(PAD53-P-Pad1)") (class "Default")
      (node (ref "PAD53") (pin "1") (pinfunction "P_1") (pintype "passive"))
    )
    (net (code "146") (name "unconnected-(PAD54-P-Pad1)") (class "Default")
      (node (ref "PAD54") (pin "1") (pinfunction "P_1") (pintype "passive"))
    )
    (net (code "147") (name "unconnected-(PAD55-P-Pad1)") (class "Default")
      (node (ref "PAD55") (pin "1") (pinfunction "P_1") (pintype "passive"))
    )
    (net (code "148") (name "unconnected-(PAD56-P-Pad1)") (class "Default")
      (node (ref "PAD56") (pin "1") (pinfunction "P_1") (pintype "passive"))
    )
    (net (code "149") (name "unconnected-(PAD57-P-Pad1)") (class "Default")
      (node (ref "PAD57") (pin "1") (pinfunction "P_1") (pintype "passive"))
    )
    (net (code "150") (name "unconnected-(PAD58-P-Pad1)") (class "Default")
      (node (ref "PAD58") (pin "1") (pinfunction "P_1") (pintype "passive"))
    )
    (net (code "151") (name "unconnected-(PAD59-P-Pad1)") (class "Default")
      (node (ref "PAD59") (pin "1") (pinfunction "P_1") (pintype "passive"))
    )
    (net (code "152") (name "unconnected-(PAD60-P-Pad1)") (class "Default")
      (node (ref "PAD60") (pin "1") (pinfunction "P_1") (pintype "passive"))
    )
    (net (code "153") (name "unconnected-(PAD61-P-Pad1)") (class "Default")
      (node (ref "PAD61") (pin "1") (pinfunction "P_1") (pintype "passive"))
    )
    (net (code "154") (name "unconnected-(PAD62-P-Pad1)") (class "Default")
      (node (ref "PAD62") (pin "1") (pinfunction "P_1") (pintype "passive"))
    )
    (net (code "155") (name "unconnected-(PAD63-P-Pad1)") (class "Default")
      (node (ref "PAD63") (pin "1") (pinfunction "P_1") (pintype "passive"))
    )
    (net (code "156") (name "unconnected-(PAD64-P-Pad1)") (class "Default")
      (node (ref "PAD64") (pin "1") (pinfunction "P_1") (pintype "passive"))
    )
    (net (code "157") (name "unconnected-(PAD65-P-Pad1)") (class "Default")
      (node (ref "PAD65") (pin "1") (pinfunction "P_1") (pintype "passive"))
    )
    (net (code "158") (name "unconnected-(PAD66-P-Pad1)") (class "Default")
      (node (ref "PAD66") (pin "1") (pinfunction "P_1") (pintype "passive"))
    )
    (net (code "159") (name "unconnected-(PAD67-P-Pad1)") (class "Default")
      (node (ref "PAD67") (pin "1") (pinfunction "P_1") (pintype "passive"))
    )
    (net (code "160") (name "unconnected-(PAD68-P-Pad1)") (class "Default")
      (node (ref "PAD68") (pin "1") (pinfunction "P_1") (pintype "passive"))
    )
    (net (code "161") (name "unconnected-(PAD69-P-Pad1)") (class "Default")
      (node (ref "PAD69") (pin "1") (pinfunction "P_1") (pintype "passive"))
    )
    (net (code "162") (name "unconnected-(PAD70-P-Pad1)") (class "Default")
      (node (ref "PAD70") (pin "1") (pinfunction "P_1") (pintype "passive"))
    )
    (net (code "163") (name "unconnected-(PAD71-P-Pad1)") (class "Default")
      (node (ref "PAD71") (pin "1") (pinfunction "P_1") (pintype "passive"))
    )
    (net (code "164") (name "unconnected-(PAD72-P-Pad1)") (class "Default")
      (node (ref "PAD72") (pin "1") (pinfunction "P_1") (pintype "passive"))
    )
    (net (code "165") (name "unconnected-(PAD74-P-Pad1)") (class "Default")
      (node (ref "PAD74") (pin "1") (pinfunction "P_1") (pintype "passive"))
    )
    (net (code "166") (name "unconnected-(PAD75-P-Pad1)") (class "Default")
      (node (ref "PAD75") (pin "1") (pinfunction "P_1") (pintype "passive"))
    )
    (net (code "167") (name "unconnected-(PAD76-P-Pad1)") (class "Default")
      (node (ref "PAD76") (pin "1") (pinfunction "P_1") (pintype "passive"))
    )
    (net (code "168") (name "unconnected-(PAD77-P-Pad1)") (class "Default")
      (node (ref "PAD77") (pin "1") (pinfunction "P_1") (pintype "passive"))
    )
    (net (code "169") (name "unconnected-(PAD78-P-Pad1)") (class "Default")
      (node (ref "PAD78") (pin "1") (pinfunction "P_1") (pintype "passive"))
    )
    (net (code "170") (name "unconnected-(PAD79-P-Pad1)") (class "Default")
      (node (ref "PAD79") (pin "1") (pinfunction "P_1") (pintype "passive"))
    )
    (net (code "171") (name "unconnected-(PAD80-P-Pad1)") (class "Default")
      (node (ref "PAD80") (pin "1") (pinfunction "P_1") (pintype "passive"))
    )
  )
)
